# User_Interface.net
KiCad netlist of a schematic drawn in Altium Designer
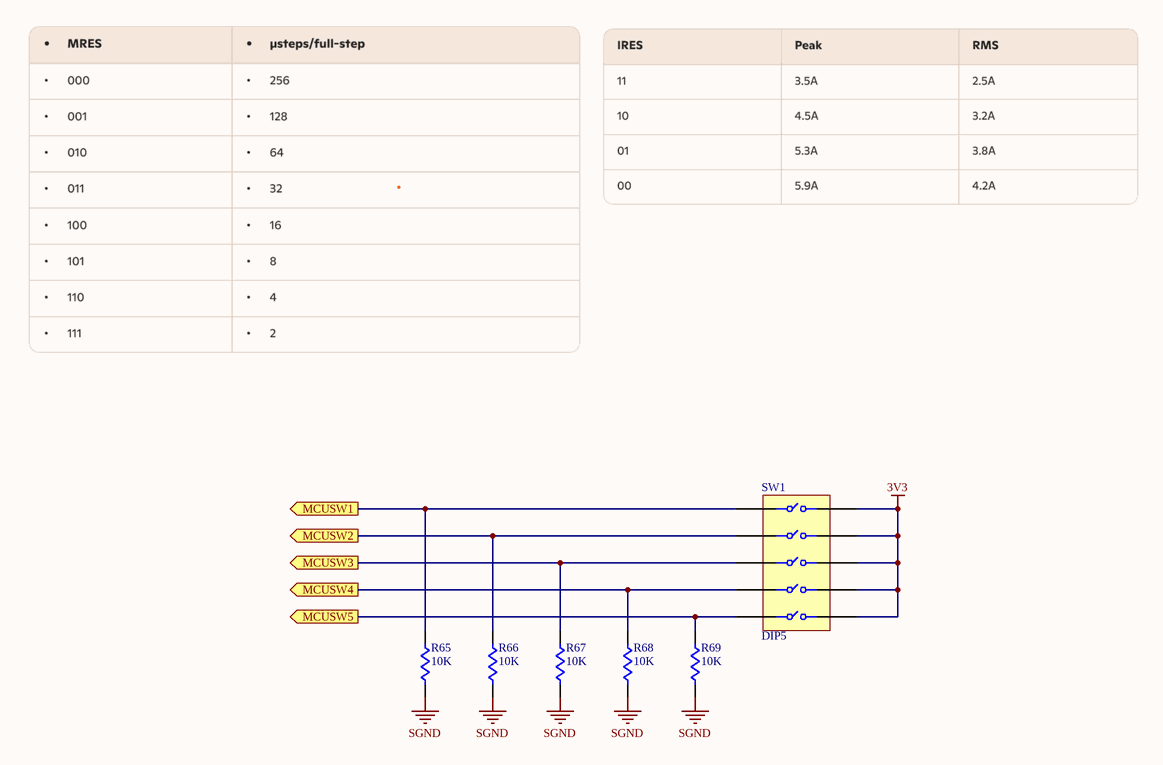
[diagram p0: User_Interface.SchDoc]

(export (version "E")
  (design (tool "Eeschema 10.0.6"))
  (components
    (comp (ref "R65")
      (value "10K")
      (footprint "RES: 0603")
      (description "RES SMD 0603")
      (libsource (lib "HZSchLib") (part "RES 0603"))
    )
    (comp (ref "R66")
      (value "10K")
      (footprint "RES: 0603")
      (description "RES SMD 0603")
      (libsource (lib "HZSchLib") (part "RES 0603"))
    )
    (comp (ref "R67")
      (value "10K")
      (footprint "RES: 0603")
      (description "RES SMD 0603")
      (libsource (lib "HZSchLib") (part "RES 0603"))
    )
    (comp (ref "R68")
      (value "10K")
      (footprint "RES: 0603")
      (description "RES SMD 0603")
      (libsource (lib "HZSchLib") (part "RES 0603"))
    )
    (comp (ref "R69")
      (value "10K")
      (footprint "RES: 0603")
      (description "RES SMD 0603")
      (libsource (lib "HZSchLib") (part "RES 0603"))
    )
    (comp (ref "SW1")
      (value "DIP5")
      (footprint "DIPSW254_5")
      (description "DIP Switch 5")
      (libsource (lib "HZSchLib") (part "DIP SW_5"))
    )
  )
  (nets
    (net (code "1") (name "/MCUSW1") (class "Default")
      (node (ref "R65") (pin "1") (pinfunction "1_1") (pintype "passive"))
      (node (ref "SW1") (pin "1") (pinfunction "COM1_1") (pintype "passive"))
    )
    (net (code "2") (name "/MCUSW2") (class "Default")
      (node (ref "R66") (pin "1") (pinfunction "1_1") (pintype "passive"))
      (node (ref "SW1") (pin "2") (pinfunction "COM2_2") (pintype "passive"))
    )
    (net (code "3") (name "/MCUSW3") (class "Default")
      (node (ref "R67") (pin "1") (pinfunction "1_1") (pintype "passive"))
      (node (ref "SW1") (pin "3") (pinfunction "COM3_3") (pintype "passive"))
    )
    (net (code "4") (name "/MCUSW4") (class "Default")
      (node (ref "R68") (pin "1") (pinfunction "1_1") (pintype "passive"))
      (node (ref "SW1") (pin "4") (pinfunction "COM4_4") (pintype "passive"))
    )
    (net (code "5") (name "/MCUSW5") (class "Default")
      (node (ref "R69") (pin "1") (pinfunction "1_1") (pintype "passive"))
      (node (ref "SW1") (pin "5") (pinfunction "COM5_5") (pintype "passive"))
    )
    (net (code "6") (name "3V3") (class "Default")
      (node (ref "SW1") (pin "10") (pinfunction "NO_1_10") (pintype "passive"))
      (node (ref "SW1") (pin "6") (pinfunction "NO_5_6") (pintype "passive"))
      (node (ref "SW1") (pin "7") (pinfunction "NO_4_7") (pintype "passive"))
      (node (ref "SW1") (pin "8") (pinfunction "NO_3_8") (pintype "passive"))
      (node (ref "SW1") (pin "9") (pinfunction "NO_2_9") (pintype "passive"))
    )
    (net (code "7") (name "SGND") (class "Default")
      (node (ref "R65") (pin "2") (pinfunction "2_2") (pintype "passive"))
      (node (ref "R66") (pin "2") (pinfunction "2_2") (pintype "passive"))
      (node (ref "R67") (pin "2") (pinfunction "2_2") (pintype "passive"))
      (node (ref "R68") (pin "2") (pinfunction "2_2") (pintype "passive"))
      (node (ref "R69") (pin "2") (pinfunction "2_2") (pintype "passive"))
    )
  )
)
